# Converter.net
KiCad netlist of a schematic drawn in Altium Designer
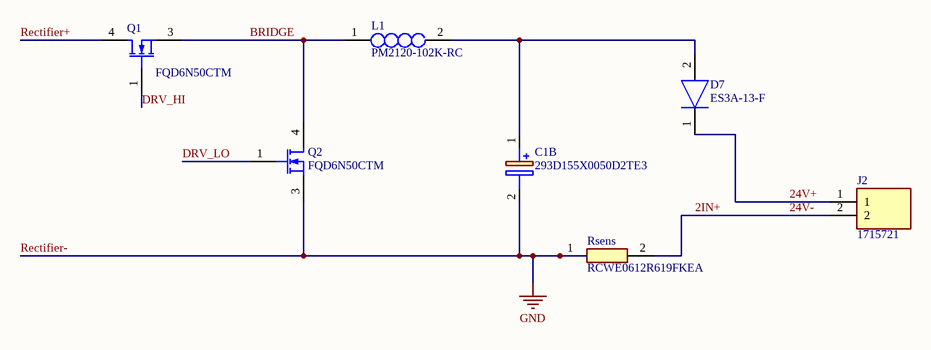
[diagram p0: Converter.SchDoc]

(export (version "E")
  (design (tool "Eeschema 10.0.6"))
  (components
    (comp (ref "C1B")
      (value "293D155X0050D2TE3")
      (footprint "SamacSys:CAPPM7343X310N")
      (description "Capacitor Polarised")
      (libsource (lib "*") (part "293D155X0050D2TE3"))
    )
    (comp (ref "D7")
      (value "ES3A-13-F")
      (footprint "SamacSys:DIOM7959X250N")
      (description "Diode")
      (fields (field (name "MOUSER PART NUMBER") "621-ES3A-F"))
      (libsource (lib "*") (part "ES3A-13-F"))
    )
    (comp (ref "J2")
      (value "1715721")
      (footprint "SamacSys:1715721")
      (description "Connector")
      (fields (field (name "MOUSER PART NUMBER") "651-1715721"))
      (libsource (lib "*") (part "1715721"))
    )
    (comp (ref "L1")
      (value "PM2120-102K-RC")
      (footprint "SamacSys:PM2120271KRC")
      (description "Inductor")
      (libsource (lib "*") (part "PM2120-102K-RC"))
    )
    (comp (ref "Q1")
      (value "FQD6N50CTM")
      (footprint "DPAK3")
      (description "Transistor, Mosfet, N-Channel, 500V V(Br)Dss, 4.5A I(D), To-252Aa")
      (fields (field (name "MANUFACTURER") "ON Semiconductor / Fairchild"))
      (libsource (lib "Schlib1") (part "FQD6N50CTM"))
    )
    (comp (ref "Q2")
      (value "FQD6N50CTM")
      (footprint "DPAK3")
      (description "Transistor, Mosfet, N-Channel, 500V V(Br)Dss, 4.5A I(D), To-252Aa")
      (fields (field (name "MANUFACTURER") "ON Semiconductor / Fairchild"))
      (libsource (lib "Schlib1") (part "FQD6N50CTM"))
    )
    (comp (ref "Rsens")
      (value "RCWE0612R619FKEA")
      (footprint "SamacSys:RESC1632X70N")
      (description "Resistor")
      (fields (field (name "MOUSER PART NUMBER") "71-RCWE0612R619FKEA"))
      (libsource (lib "*") (part "RCWE0612R619FKEA"))
    )
  )
  (nets
    (net (code "1") (name "/24V+") (class "Default")
      (node (ref "D7") (pin "1") (pinfunction "K_1") (pintype "passive"))
      (node (ref "J2") (pin "1") (pinfunction "1_1") (pintype "passive"))
    )
    (net (code "2") (name "/24V-") (class "Default")
      (node (ref "J2") (pin "2") (pinfunction "2_2") (pintype "passive"))
      (node (ref "Rsens") (pin "2") (pinfunction "2_2") (pintype "passive"))
    )
    (net (code "3") (name "/BRIDGE") (class "Default")
      (node (ref "L1") (pin "1") (pinfunction "1_1") (pintype "passive"))
      (node (ref "Q1") (pin "3") (pinfunction "S_3") (pintype "passive"))
      (node (ref "Q2") (pin "4") (pinfunction "D_4") (pintype "passive"))
    )
    (net (code "4") (name "/DRV_HI") (class "Default")
      (node (ref "Q1") (pin "1") (pinfunction "G_1") (pintype "passive"))
    )
    (net (code "5") (name "/DRV_LO") (class "Default")
      (node (ref "Q2") (pin "1") (pinfunction "G_1") (pintype "passive"))
    )
    (net (code "6") (name "/Rectifier+") (class "Default")
      (node (ref "Q1") (pin "4") (pinfunction "D_4") (pintype "passive"))
    )
    (net (code "7") (name "GND") (class "Default")
      (node (ref "C1B") (pin "2") (pinfunction "-_2") (pintype "passive"))
      (node (ref "Q2") (pin "3") (pinfunction "S_3") (pintype "passive"))
      (node (ref "Rsens") (pin "1") (pinfunction "1_1") (pintype "passive"))
    )
    (net (code "8") (name "Net-(C1B-+)") (class "Default")
      (node (ref "C1B") (pin "1") (pinfunction "+_1") (pintype "passive"))
      (node (ref "D7") (pin "2") (pinfunction "A_2") (pintype "passive"))
      (node (ref "L1") (pin "2") (pinfunction "2_2") (pintype "passive"))
    )
  )
)
